# e.net
KiCad netlist of a schematic drawn in EAGLE
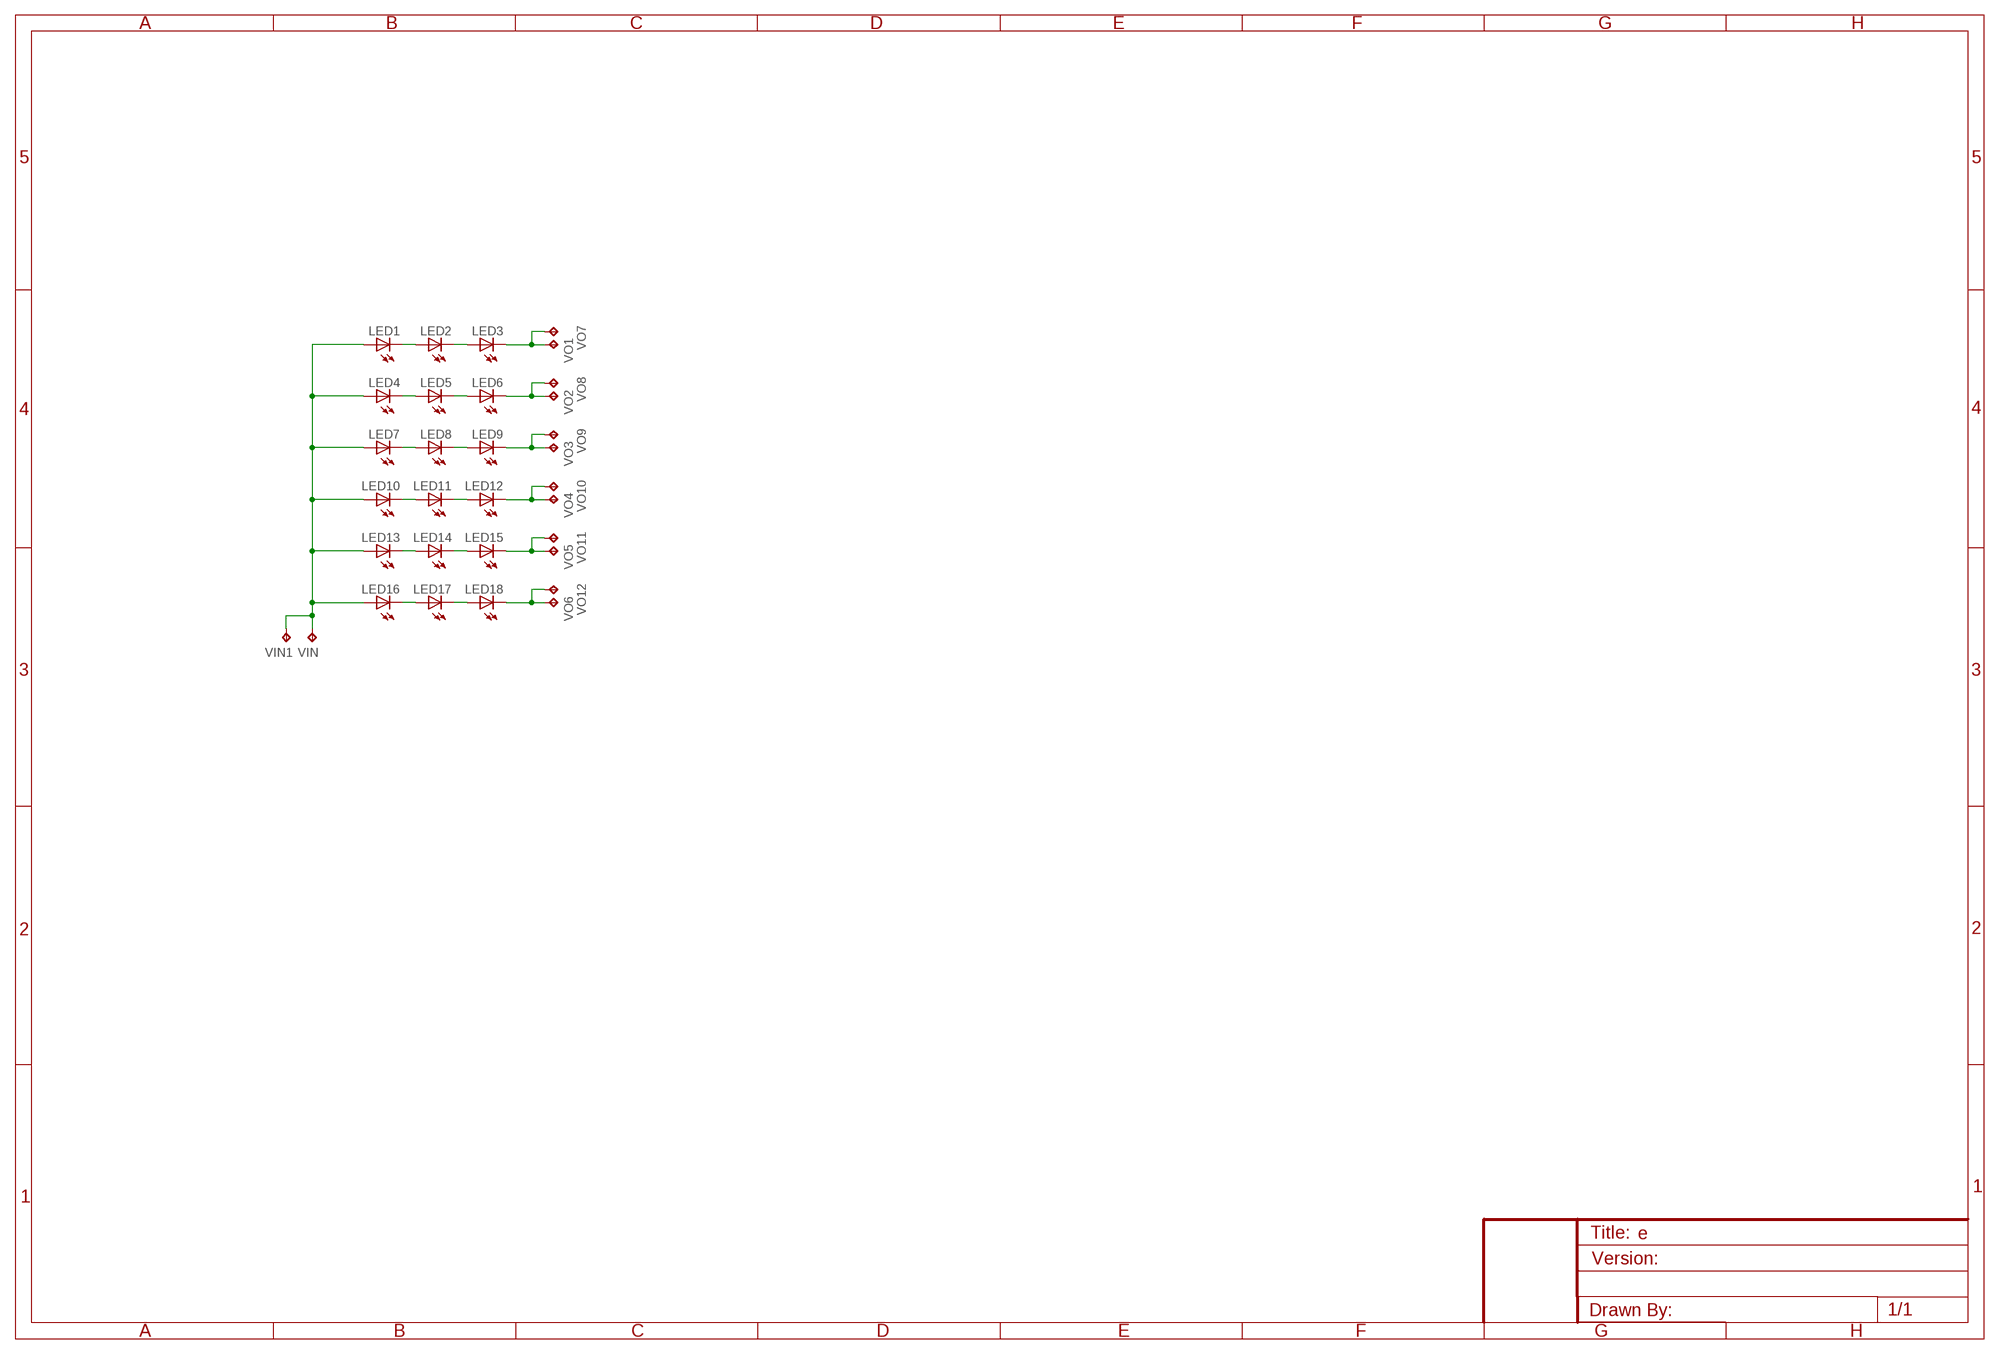
[diagram p0: schematic, sheet 1]

(export (version "E")
  (design (tool "Eeschema 10.0.6"))
  (components
    (comp (ref "LED1")
      (value "LED0805")
      (footprint "eagle-import:LED_0805")
      (libsource (lib "eagle-import") (part "LED0805"))
    )
    (comp (ref "LED2")
      (value "LED0805")
      (footprint "eagle-import:LED_0805")
      (libsource (lib "eagle-import") (part "LED0805"))
    )
    (comp (ref "LED3")
      (value "LED0805")
      (footprint "eagle-import:LED_0805")
      (libsource (lib "eagle-import") (part "LED0805"))
    )
    (comp (ref "LED4")
      (value "LED0805")
      (footprint "eagle-import:LED_0805")
      (libsource (lib "eagle-import") (part "LED0805"))
    )
    (comp (ref "LED5")
      (value "LED0805")
      (footprint "eagle-import:LED_0805")
      (libsource (lib "eagle-import") (part "LED0805"))
    )
    (comp (ref "LED6")
      (value "LED0805")
      (footprint "eagle-import:LED_0805")
      (libsource (lib "eagle-import") (part "LED0805"))
    )
    (comp (ref "LED7")
      (value "LED0805")
      (footprint "eagle-import:LED_0805")
      (libsource (lib "eagle-import") (part "LED0805"))
    )
    (comp (ref "LED8")
      (value "LED0805")
      (footprint "eagle-import:LED_0805")
      (libsource (lib "eagle-import") (part "LED0805"))
    )
    (comp (ref "LED9")
      (value "LED0805")
      (footprint "eagle-import:LED_0805")
      (libsource (lib "eagle-import") (part "LED0805"))
    )
    (comp (ref "LED10")
      (value "LED0805")
      (footprint "eagle-import:LED_0805")
      (libsource (lib "eagle-import") (part "LED0805"))
    )
    (comp (ref "LED11")
      (value "LED0805")
      (footprint "eagle-import:LED_0805")
      (libsource (lib "eagle-import") (part "LED0805"))
    )
    (comp (ref "LED12")
      (value "LED0805")
      (footprint "eagle-import:LED_0805")
      (libsource (lib "eagle-import") (part "LED0805"))
    )
    (comp (ref "LED13")
      (value "LED0805")
      (footprint "eagle-import:LED_0805")
      (libsource (lib "eagle-import") (part "LED0805"))
    )
    (comp (ref "LED14")
      (value "LED0805")
      (footprint "eagle-import:LED_0805")
      (libsource (lib "eagle-import") (part "LED0805"))
    )
    (comp (ref "LED15")
      (value "LED0805")
      (footprint "eagle-import:LED_0805")
      (libsource (lib "eagle-import") (part "LED0805"))
    )
    (comp (ref "LED16")
      (value "LED0805")
      (footprint "eagle-import:LED_0805")
      (libsource (lib "eagle-import") (part "LED0805"))
    )
    (comp (ref "LED17")
      (value "LED0805")
      (footprint "eagle-import:LED_0805")
      (libsource (lib "eagle-import") (part "LED0805"))
    )
    (comp (ref "LED18")
      (value "LED0805")
      (footprint "eagle-import:LED_0805")
      (libsource (lib "eagle-import") (part "LED0805"))
    )
    (comp (ref "VIN")
      (value "TEST_POINTPAD1-20")
      (footprint "eagle-import:P1-20")
      (libsource (lib "eagle-import") (part "TEST_POINTPAD1-20"))
    )
    (comp (ref "VIN1")
      (value "TEST_POINTPAD1-20")
      (footprint "eagle-import:P1-20")
      (libsource (lib "eagle-import") (part "TEST_POINTPAD1-20"))
    )
    (comp (ref "VO1")
      (value "TEST_POINTPAD1-20")
      (footprint "eagle-import:P1-20")
      (libsource (lib "eagle-import") (part "TEST_POINTPAD1-20"))
    )
    (comp (ref "VO2")
      (value "TEST_POINTPAD1-20")
      (footprint "eagle-import:P1-20")
      (libsource (lib "eagle-import") (part "TEST_POINTPAD1-20"))
    )
    (comp (ref "VO3")
      (value "TEST_POINTPAD1-20")
      (footprint "eagle-import:P1-20")
      (libsource (lib "eagle-import") (part "TEST_POINTPAD1-20"))
    )
    (comp (ref "VO4")
      (value "TEST_POINTPAD1-20")
      (footprint "eagle-import:P1-20")
      (libsource (lib "eagle-import") (part "TEST_POINTPAD1-20"))
    )
    (comp (ref "VO5")
      (value "TEST_POINTPAD1-20")
      (footprint "eagle-import:P1-20")
      (libsource (lib "eagle-import") (part "TEST_POINTPAD1-20"))
    )
    (comp (ref "VO6")
      (value "TEST_POINTPAD1-20")
      (footprint "eagle-import:P1-20")
      (libsource (lib "eagle-import") (part "TEST_POINTPAD1-20"))
    )
    (comp (ref "VO7")
      (value "TEST_POINTPAD1-20")
      (footprint "eagle-import:P1-20")
      (libsource (lib "eagle-import") (part "TEST_POINTPAD1-20"))
    )
    (comp (ref "VO8")
      (value "TEST_POINTPAD1-20")
      (footprint "eagle-import:P1-20")
      (libsource (lib "eagle-import") (part "TEST_POINTPAD1-20"))
    )
    (comp (ref "VO9")
      (value "TEST_POINTPAD1-20")
      (footprint "eagle-import:P1-20")
      (libsource (lib "eagle-import") (part "TEST_POINTPAD1-20"))
    )
    (comp (ref "VO10")
      (value "TEST_POINTPAD1-20")
      (footprint "eagle-import:P1-20")
      (libsource (lib "eagle-import") (part "TEST_POINTPAD1-20"))
    )
    (comp (ref "VO11")
      (value "TEST_POINTPAD1-20")
      (footprint "eagle-import:P1-20")
      (libsource (lib "eagle-import") (part "TEST_POINTPAD1-20"))
    )
    (comp (ref "VO12")
      (value "TEST_POINTPAD1-20")
      (footprint "eagle-import:P1-20")
      (libsource (lib "eagle-import") (part "TEST_POINTPAD1-20"))
    )
  )
  (nets
    (net (code "1") (name "Net-(LED1-PadA)") (class "Default")
      (node (ref "LED1") (pin "A") (pinfunction "A_A") (pintype "passive"))
      (node (ref "LED10") (pin "A") (pinfunction "A_A") (pintype "passive"))
      (node (ref "LED13") (pin "A") (pinfunction "A_A") (pintype "passive"))
      (node (ref "LED16") (pin "A") (pinfunction "A_A") (pintype "passive"))
      (node (ref "LED4") (pin "A") (pinfunction "A_A") (pintype "passive"))
      (node (ref "LED7") (pin "A") (pinfunction "A_A") (pintype "passive"))
      (node (ref "VIN") (pin "TP") (pinfunction "TP_TP") (pintype "input"))
      (node (ref "VIN1") (pin "TP") (pinfunction "TP_TP") (pintype "input"))
    )
    (net (code "2") (name "Net-(LED1-PadC)") (class "Default")
      (node (ref "LED1") (pin "C") (pinfunction "C_C") (pintype "passive"))
      (node (ref "LED2") (pin "A") (pinfunction "A_A") (pintype "passive"))
    )
    (net (code "3") (name "Net-(LED2-PadC)") (class "Default")
      (node (ref "LED2") (pin "C") (pinfunction "C_C") (pintype "passive"))
      (node (ref "LED3") (pin "A") (pinfunction "A_A") (pintype "passive"))
    )
    (net (code "4") (name "Net-(LED3-PadC)") (class "Default")
      (node (ref "LED3") (pin "C") (pinfunction "C_C") (pintype "passive"))
      (node (ref "VO1") (pin "TP") (pinfunction "TP_TP") (pintype "input"))
      (node (ref "VO7") (pin "TP") (pinfunction "TP_TP") (pintype "input"))
    )
    (net (code "5") (name "Net-(LED4-PadC)") (class "Default")
      (node (ref "LED4") (pin "C") (pinfunction "C_C") (pintype "passive"))
      (node (ref "LED5") (pin "A") (pinfunction "A_A") (pintype "passive"))
    )
    (net (code "6") (name "Net-(LED5-PadC)") (class "Default")
      (node (ref "LED5") (pin "C") (pinfunction "C_C") (pintype "passive"))
      (node (ref "LED6") (pin "A") (pinfunction "A_A") (pintype "passive"))
    )
    (net (code "7") (name "Net-(LED6-PadC)") (class "Default")
      (node (ref "LED6") (pin "C") (pinfunction "C_C") (pintype "passive"))
      (node (ref "VO2") (pin "TP") (pinfunction "TP_TP") (pintype "input"))
      (node (ref "VO8") (pin "TP") (pinfunction "TP_TP") (pintype "input"))
    )
    (net (code "8") (name "Net-(LED7-PadC)") (class "Default")
      (node (ref "LED7") (pin "C") (pinfunction "C_C") (pintype "passive"))
      (node (ref "LED8") (pin "A") (pinfunction "A_A") (pintype "passive"))
    )
    (net (code "9") (name "Net-(LED8-PadC)") (class "Default")
      (node (ref "LED8") (pin "C") (pinfunction "C_C") (pintype "passive"))
      (node (ref "LED9") (pin "A") (pinfunction "A_A") (pintype "passive"))
    )
    (net (code "10") (name "Net-(LED9-PadC)") (class "Default")
      (node (ref "LED9") (pin "C") (pinfunction "C_C") (pintype "passive"))
      (node (ref "VO3") (pin "TP") (pinfunction "TP_TP") (pintype "input"))
      (node (ref "VO9") (pin "TP") (pinfunction "TP_TP") (pintype "input"))
    )
    (net (code "11") (name "Net-(LED10-PadC)") (class "Default")
      (node (ref "LED10") (pin "C") (pinfunction "C_C") (pintype "passive"))
      (node (ref "LED11") (pin "A") (pinfunction "A_A") (pintype "passive"))
    )
    (net (code "12") (name "Net-(LED11-PadC)") (class "Default")
      (node (ref "LED11") (pin "C") (pinfunction "C_C") (pintype "passive"))
      (node (ref "LED12") (pin "A") (pinfunction "A_A") (pintype "passive"))
    )
    (net (code "13") (name "Net-(LED12-PadC)") (class "Default")
      (node (ref "LED12") (pin "C") (pinfunction "C_C") (pintype "passive"))
      (node (ref "VO10") (pin "TP") (pinfunction "TP_TP") (pintype "input"))
      (node (ref "VO4") (pin "TP") (pinfunction "TP_TP") (pintype "input"))
    )
    (net (code "14") (name "Net-(LED13-PadC)") (class "Default")
      (node (ref "LED13") (pin "C") (pinfunction "C_C") (pintype "passive"))
      (node (ref "LED14") (pin "A") (pinfunction "A_A") (pintype "passive"))
    )
    (net (code "15") (name "Net-(LED14-PadC)") (class "Default")
      (node (ref "LED14") (pin "C") (pinfunction "C_C") (pintype "passive"))
      (node (ref "LED15") (pin "A") (pinfunction "A_A") (pintype "passive"))
    )
    (net (code "16") (name "Net-(LED15-PadC)") (class "Default")
      (node (ref "LED15") (pin "C") (pinfunction "C_C") (pintype "passive"))
      (node (ref "VO11") (pin "TP") (pinfunction "TP_TP") (pintype "input"))
      (node (ref "VO5") (pin "TP") (pinfunction "TP_TP") (pintype "input"))
    )
    (net (code "17") (name "Net-(LED16-PadC)") (class "Default")
      (node (ref "LED16") (pin "C") (pinfunction "C_C") (pintype "passive"))
      (node (ref "LED17") (pin "A") (pinfunction "A_A") (pintype "passive"))
    )
    (net (code "18") (name "Net-(LED17-PadC)") (class "Default")
      (node (ref "LED17") (pin "C") (pinfunction "C_C") (pintype "passive"))
      (node (ref "LED18") (pin "A") (pinfunction "A_A") (pintype "passive"))
    )
    (net (code "19") (name "Net-(LED18-PadC)") (class "Default")
      (node (ref "LED18") (pin "C") (pinfunction "C_C") (pintype "passive"))
      (node (ref "VO12") (pin "TP") (pinfunction "TP_TP") (pintype "input"))
      (node (ref "VO6") (pin "TP") (pinfunction "TP_TP") (pintype "input"))
    )
  )
)
